# base.net
KiCad netlist of a schematic drawn in EAGLE
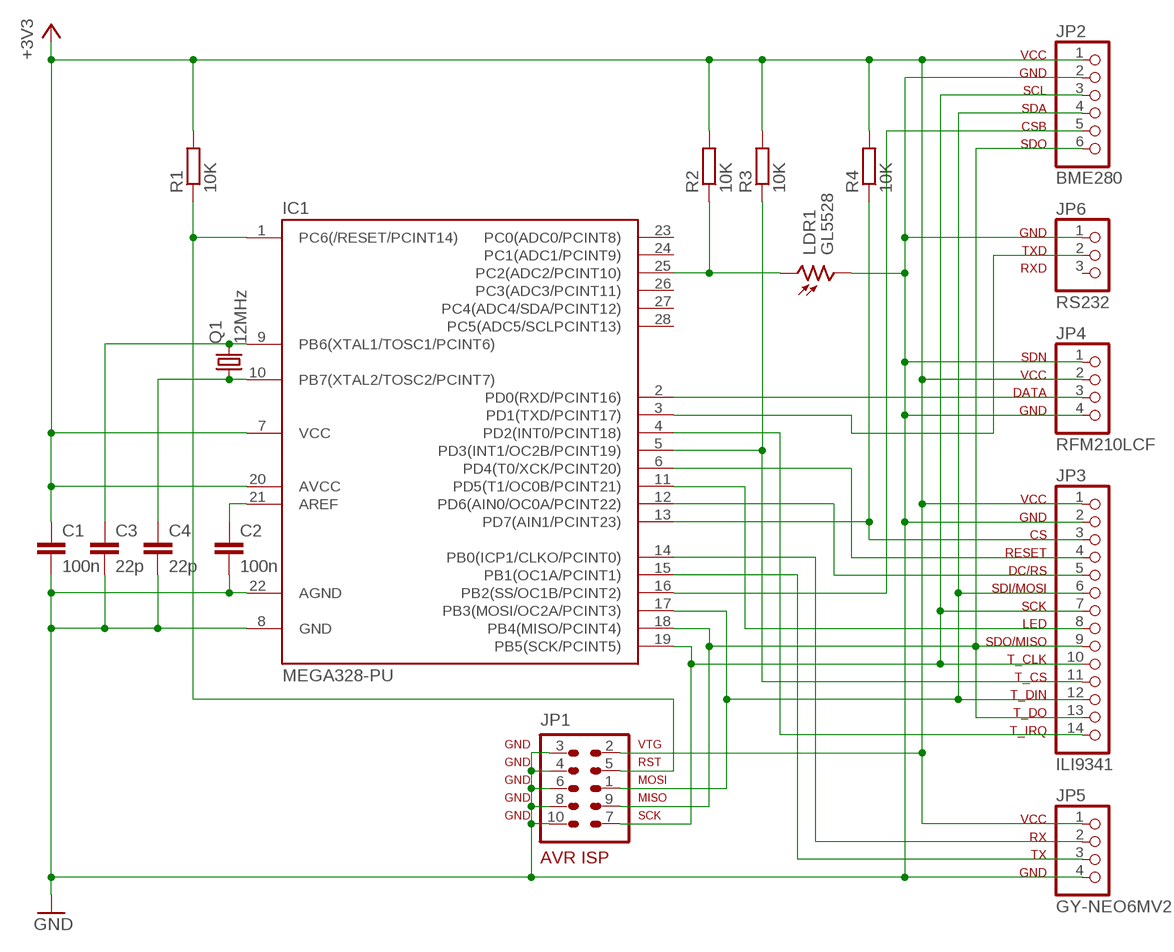
[diagram p0: schematic, sheet 1]

(export (version "E")
  (design (tool "Eeschema 10.0.6"))
  (components
    (comp (ref "C1")
      (value "100n")
      (footprint "eagle-import:C025-025X050")
      (libsource (lib "eagle-import") (part "C-EU025-025X050"))
    )
    (comp (ref "C2")
      (value "100n")
      (footprint "eagle-import:C025-025X050")
      (libsource (lib "eagle-import") (part "C-EU025-025X050"))
    )
    (comp (ref "C3")
      (value "22p")
      (footprint "eagle-import:C025-025X050")
      (libsource (lib "eagle-import") (part "C-EU025-025X050"))
    )
    (comp (ref "C4")
      (value "22p")
      (footprint "eagle-import:C025-025X050")
      (libsource (lib "eagle-import") (part "C-EU025-025X050"))
    )
    (comp (ref "IC1")
      (value "MEGA328-PU")
      (footprint "eagle-import:DIL28-3")
      (libsource (lib "eagle-import") (part "MEGA48/88/168-PU"))
    )
    (comp (ref "JP1")
      (value "AVR-ISP-10")
      (footprint "eagle-import:AVR-ISP-10")
      (libsource (lib "eagle-import") (part "AVR-ISP-10"))
    )
    (comp (ref "JP2")
      (value "BME280")
      (footprint "eagle-import:1X06")
      (libsource (lib "eagle-import") (part "PINHD-1X6"))
    )
    (comp (ref "JP3")
      (value "ILI9341")
      (footprint "eagle-import:1X14")
      (libsource (lib "eagle-import") (part "PINHD-1X14"))
    )
    (comp (ref "JP4")
      (value "RFM210LCF")
      (footprint "eagle-import:1X04")
      (libsource (lib "eagle-import") (part "PINHD-1X4"))
    )
    (comp (ref "JP5")
      (value "GY-NEO6MV2")
      (footprint "eagle-import:1X04")
      (libsource (lib "eagle-import") (part "PINHD-1X4"))
    )
    (comp (ref "JP6")
      (value "RS232")
      (footprint "eagle-import:1X03")
      (libsource (lib "eagle-import") (part "PINHD-1X3"))
    )
    (comp (ref "LDR1")
      (value "GL5528")
      (footprint "eagle-import:TO46-VT200")
      (libsource (lib "eagle-import") (part "VT20N1"))
    )
    (comp (ref "Q1")
      (value "12MHz")
      (footprint "eagle-import:HC49U-V")
      (libsource (lib "eagle-import") (part "CRYSTALHC49U-V"))
    )
    (comp (ref "R1")
      (value "10K")
      (footprint "eagle-import:0204_7")
      (libsource (lib "eagle-import") (part "R-EU_0204/7"))
    )
    (comp (ref "R2")
      (value "10K")
      (footprint "eagle-import:0204_7")
      (libsource (lib "eagle-import") (part "R-EU_0204/7"))
    )
    (comp (ref "R3")
      (value "10K")
      (footprint "eagle-import:0204_7")
      (libsource (lib "eagle-import") (part "R-EU_0204/7"))
    )
    (comp (ref "R4")
      (value "10K")
      (footprint "eagle-import:0204_7")
      (libsource (lib "eagle-import") (part "R-EU_0204/7"))
    )
  )
  (nets
    (net (code "1") (name "+3V3") (class "Default")
      (node (ref "C1") (pin "1") (pinfunction "1_1") (pintype "passive"))
      (node (ref "IC1") (pin "20") (pinfunction "AVCC_20") (pintype "passive"))
      (node (ref "IC1") (pin "7") (pinfunction "VCC_7") (pintype "power_in"))
      (node (ref "JP1") (pin "2") (pinfunction "2_2") (pintype "passive"))
      (node (ref "JP2") (pin "1") (pinfunction "1_1") (pintype "passive"))
      (node (ref "JP3") (pin "1") (pinfunction "1_1") (pintype "passive"))
      (node (ref "JP4") (pin "2") (pinfunction "2_2") (pintype "passive"))
      (node (ref "JP5") (pin "1") (pinfunction "1_1") (pintype "passive"))
      (node (ref "R1") (pin "2") (pinfunction "2_2") (pintype "passive"))
      (node (ref "R2") (pin "2") (pinfunction "2_2") (pintype "passive"))
      (node (ref "R3") (pin "2") (pinfunction "2_2") (pintype "passive"))
      (node (ref "R4") (pin "2") (pinfunction "2_2") (pintype "passive"))
    )
    (net (code "2") (name "GND") (class "Default")
      (node (ref "C1") (pin "2") (pinfunction "2_2") (pintype "passive"))
      (node (ref "C2") (pin "2") (pinfunction "2_2") (pintype "passive"))
      (node (ref "C3") (pin "2") (pinfunction "2_2") (pintype "passive"))
      (node (ref "C4") (pin "2") (pinfunction "2_2") (pintype "passive"))
      (node (ref "IC1") (pin "22") (pinfunction "AGND_22") (pintype "power_in"))
      (node (ref "IC1") (pin "8") (pinfunction "GND_8") (pintype "power_in"))
      (node (ref "JP1") (pin "10") (pinfunction "10_10") (pintype "passive"))
      (node (ref "JP1") (pin "3") (pinfunction "3_3") (pintype "passive"))
      (node (ref "JP1") (pin "4") (pinfunction "4_4") (pintype "passive"))
      (node (ref "JP1") (pin "6") (pinfunction "6_6") (pintype "passive"))
      (node (ref "JP1") (pin "8") (pinfunction "8_8") (pintype "passive"))
      (node (ref "JP2") (pin "2") (pinfunction "2_2") (pintype "passive"))
      (node (ref "JP3") (pin "2") (pinfunction "2_2") (pintype "passive"))
      (node (ref "JP4") (pin "1") (pinfunction "1_1") (pintype "passive"))
      (node (ref "JP4") (pin "4") (pinfunction "4_4") (pintype "passive"))
      (node (ref "JP5") (pin "4") (pinfunction "4_4") (pintype "passive"))
      (node (ref "JP6") (pin "1") (pinfunction "1_1") (pintype "passive"))
      (node (ref "LDR1") (pin "2") (pinfunction "2_2") (pintype "passive"))
    )
    (net (code "3") (name "Net-(IC1-AREF)") (class "Default")
      (node (ref "C2") (pin "1") (pinfunction "1_1") (pintype "passive"))
      (node (ref "IC1") (pin "21") (pinfunction "AREF_21") (pintype "passive"))
    )
    (net (code "4") (name "Net-(IC1-PB0(ICP1{slash}CLKO{slash}PCINT0))") (class "Default")
      (node (ref "IC1") (pin "14") (pinfunction "PB0(ICP1/CLKO/PCINT0)_14") (pintype "bidirectional"))
      (node (ref "JP5") (pin "2") (pinfunction "2_2") (pintype "passive"))
    )
    (net (code "5") (name "Net-(IC1-PB1(OC1A{slash}PCINT1))") (class "Default")
      (node (ref "IC1") (pin "15") (pinfunction "PB1(OC1A/PCINT1)_15") (pintype "bidirectional"))
      (node (ref "JP5") (pin "3") (pinfunction "3_3") (pintype "passive"))
    )
    (net (code "6") (name "Net-(IC1-PB2(SS{slash}OC1B{slash}PCINT2))") (class "Default")
      (node (ref "IC1") (pin "16") (pinfunction "PB2(SS/OC1B/PCINT2)_16") (pintype "bidirectional"))
      (node (ref "JP2") (pin "5") (pinfunction "5_5") (pintype "passive"))
    )
    (net (code "7") (name "Net-(IC1-PB3(MOSI{slash}OC2A{slash}PCINT3))") (class "Default")
      (node (ref "IC1") (pin "17") (pinfunction "PB3(MOSI/OC2A/PCINT3)_17") (pintype "bidirectional"))
      (node (ref "JP1") (pin "1") (pinfunction "1_1") (pintype "passive"))
      (node (ref "JP2") (pin "4") (pinfunction "4_4") (pintype "passive"))
      (node (ref "JP3") (pin "12") (pinfunction "12_12") (pintype "passive"))
      (node (ref "JP3") (pin "6") (pinfunction "6_6") (pintype "passive"))
    )
    (net (code "8") (name "Net-(IC1-PB4(MISO{slash}PCINT4))") (class "Default")
      (node (ref "IC1") (pin "18") (pinfunction "PB4(MISO/PCINT4)_18") (pintype "bidirectional"))
      (node (ref "JP1") (pin "9") (pinfunction "9_9") (pintype "passive"))
      (node (ref "JP2") (pin "6") (pinfunction "6_6") (pintype "passive"))
      (node (ref "JP3") (pin "13") (pinfunction "13_13") (pintype "passive"))
      (node (ref "JP3") (pin "9") (pinfunction "9_9") (pintype "passive"))
    )
    (net (code "9") (name "Net-(IC1-PB5(SCK{slash}PCINT5))") (class "Default")
      (node (ref "IC1") (pin "19") (pinfunction "PB5(SCK/PCINT5)_19") (pintype "bidirectional"))
      (node (ref "JP1") (pin "7") (pinfunction "7_7") (pintype "passive"))
      (node (ref "JP2") (pin "3") (pinfunction "3_3") (pintype "passive"))
      (node (ref "JP3") (pin "10") (pinfunction "10_10") (pintype "passive"))
      (node (ref "JP3") (pin "7") (pinfunction "7_7") (pintype "passive"))
    )
    (net (code "10") (name "Net-(IC1-PB6(XTAL1{slash}TOSC1{slash}PCINT6))") (class "Default")
      (node (ref "C3") (pin "1") (pinfunction "1_1") (pintype "passive"))
      (node (ref "IC1") (pin "9") (pinfunction "PB6(XTAL1/TOSC1/PCINT6)_9") (pintype "bidirectional"))
      (node (ref "Q1") (pin "2") (pinfunction "2_2") (pintype "passive"))
    )
    (net (code "11") (name "Net-(IC1-PB7(XTAL2{slash}TOSC2{slash}PCINT7))") (class "Default")
      (node (ref "C4") (pin "1") (pinfunction "1_1") (pintype "passive"))
      (node (ref "IC1") (pin "10") (pinfunction "PB7(XTAL2/TOSC2/PCINT7)_10") (pintype "bidirectional"))
      (node (ref "Q1") (pin "1") (pinfunction "1_1") (pintype "passive"))
    )
    (net (code "12") (name "Net-(IC1-PC2(ADC2{slash}PCINT10))") (class "Default")
      (node (ref "IC1") (pin "25") (pinfunction "PC2(ADC2/PCINT10)_25") (pintype "bidirectional"))
      (node (ref "LDR1") (pin "1") (pinfunction "1_1") (pintype "passive"))
      (node (ref "R2") (pin "1") (pinfunction "1_1") (pintype "passive"))
    )
    (net (code "13") (name "Net-(IC1-PC6({slash}RESET{slash}PCINT14))") (class "Default")
      (node (ref "IC1") (pin "1") (pinfunction "PC6(/RESET/PCINT14)_1") (pintype "bidirectional"))
      (node (ref "JP1") (pin "5") (pinfunction "5_5") (pintype "passive"))
      (node (ref "R1") (pin "1") (pinfunction "1_1") (pintype "passive"))
    )
    (net (code "14") (name "Net-(IC1-PD0(RXD{slash}PCINT16))") (class "Default")
      (node (ref "IC1") (pin "2") (pinfunction "PD0(RXD/PCINT16)_2") (pintype "bidirectional"))
      (node (ref "JP4") (pin "3") (pinfunction "3_3") (pintype "passive"))
    )
    (net (code "15") (name "Net-(IC1-PD1(TXD{slash}PCINT17))") (class "Default")
      (node (ref "IC1") (pin "3") (pinfunction "PD1(TXD/PCINT17)_3") (pintype "bidirectional"))
      (node (ref "JP6") (pin "2") (pinfunction "2_2") (pintype "passive"))
    )
    (net (code "16") (name "Net-(IC1-PD2(INT0{slash}PCINT18))") (class "Default")
      (node (ref "IC1") (pin "4") (pinfunction "PD2(INT0/PCINT18)_4") (pintype "bidirectional"))
      (node (ref "JP3") (pin "14") (pinfunction "14_14") (pintype "passive"))
    )
    (net (code "17") (name "Net-(IC1-PD3(INT1{slash}OC2B{slash}PCINT19))") (class "Default")
      (node (ref "IC1") (pin "5") (pinfunction "PD3(INT1/OC2B/PCINT19)_5") (pintype "bidirectional"))
      (node (ref "JP3") (pin "11") (pinfunction "11_11") (pintype "passive"))
      (node (ref "R3") (pin "1") (pinfunction "1_1") (pintype "passive"))
    )
    (net (code "18") (name "Net-(IC1-PD4(T0{slash}XCK{slash}PCINT20))") (class "Default")
      (node (ref "IC1") (pin "6") (pinfunction "PD4(T0/XCK/PCINT20)_6") (pintype "bidirectional"))
      (node (ref "JP3") (pin "4") (pinfunction "4_4") (pintype "passive"))
    )
    (net (code "19") (name "Net-(IC1-PD5(T1{slash}OC0B{slash}PCINT21))") (class "Default")
      (node (ref "IC1") (pin "11") (pinfunction "PD5(T1/OC0B/PCINT21)_11") (pintype "bidirectional"))
      (node (ref "JP3") (pin "8") (pinfunction "8_8") (pintype "passive"))
    )
    (net (code "20") (name "Net-(IC1-PD6(AIN0{slash}OC0A{slash}PCINT22))") (class "Default")
      (node (ref "IC1") (pin "12") (pinfunction "PD6(AIN0/OC0A/PCINT22)_12") (pintype "bidirectional"))
      (node (ref "JP3") (pin "5") (pinfunction "5_5") (pintype "passive"))
    )
    (net (code "21") (name "Net-(IC1-PD7(AIN1{slash}PCINT23))") (class "Default")
      (node (ref "IC1") (pin "13") (pinfunction "PD7(AIN1/PCINT23)_13") (pintype "bidirectional"))
      (node (ref "JP3") (pin "3") (pinfunction "3_3") (pintype "passive"))
      (node (ref "R4") (pin "1") (pinfunction "1_1") (pintype "passive"))
    )
    (net (code "22") (name "unconnected-(IC1-PC0(ADC0{slash}PCINT8)-Pad23)") (class "Default")
      (node (ref "IC1") (pin "23") (pinfunction "PC0(ADC0/PCINT8)_23") (pintype "bidirectional"))
    )
    (net (code "23") (name "unconnected-(IC1-PC1(ADC1{slash}PCINT9)-Pad24)") (class "Default")
      (node (ref "IC1") (pin "24") (pinfunction "PC1(ADC1/PCINT9)_24") (pintype "bidirectional"))
    )
    (net (code "24") (name "unconnected-(IC1-PC3(ADC3{slash}PCINT11)-Pad26)") (class "Default")
      (node (ref "IC1") (pin "26") (pinfunction "PC3(ADC3/PCINT11)_26") (pintype "bidirectional"))
    )
    (net (code "25") (name "unconnected-(IC1-PC4(ADC4{slash}SDA{slash}PCINT12)-Pad27)") (class "Default")
      (node (ref "IC1") (pin "27") (pinfunction "PC4(ADC4/SDA/PCINT12)_27") (pintype "bidirectional"))
    )
    (net (code "26") (name "unconnected-(IC1-PC5(ADC5{slash}SCLPCINT13)-Pad28)") (class "Default")
      (node (ref "IC1") (pin "28") (pinfunction "PC5(ADC5/SCLPCINT13)_28") (pintype "bidirectional"))
    )
    (net (code "27") (name "unconnected-(JP6-Pad3)") (class "Default")
      (node (ref "JP6") (pin "3") (pinfunction "3_3") (pintype "passive"))
    )
  )
)
